# parent_altium-designer.net
KiCad netlist of a schematic drawn in Altium Designer
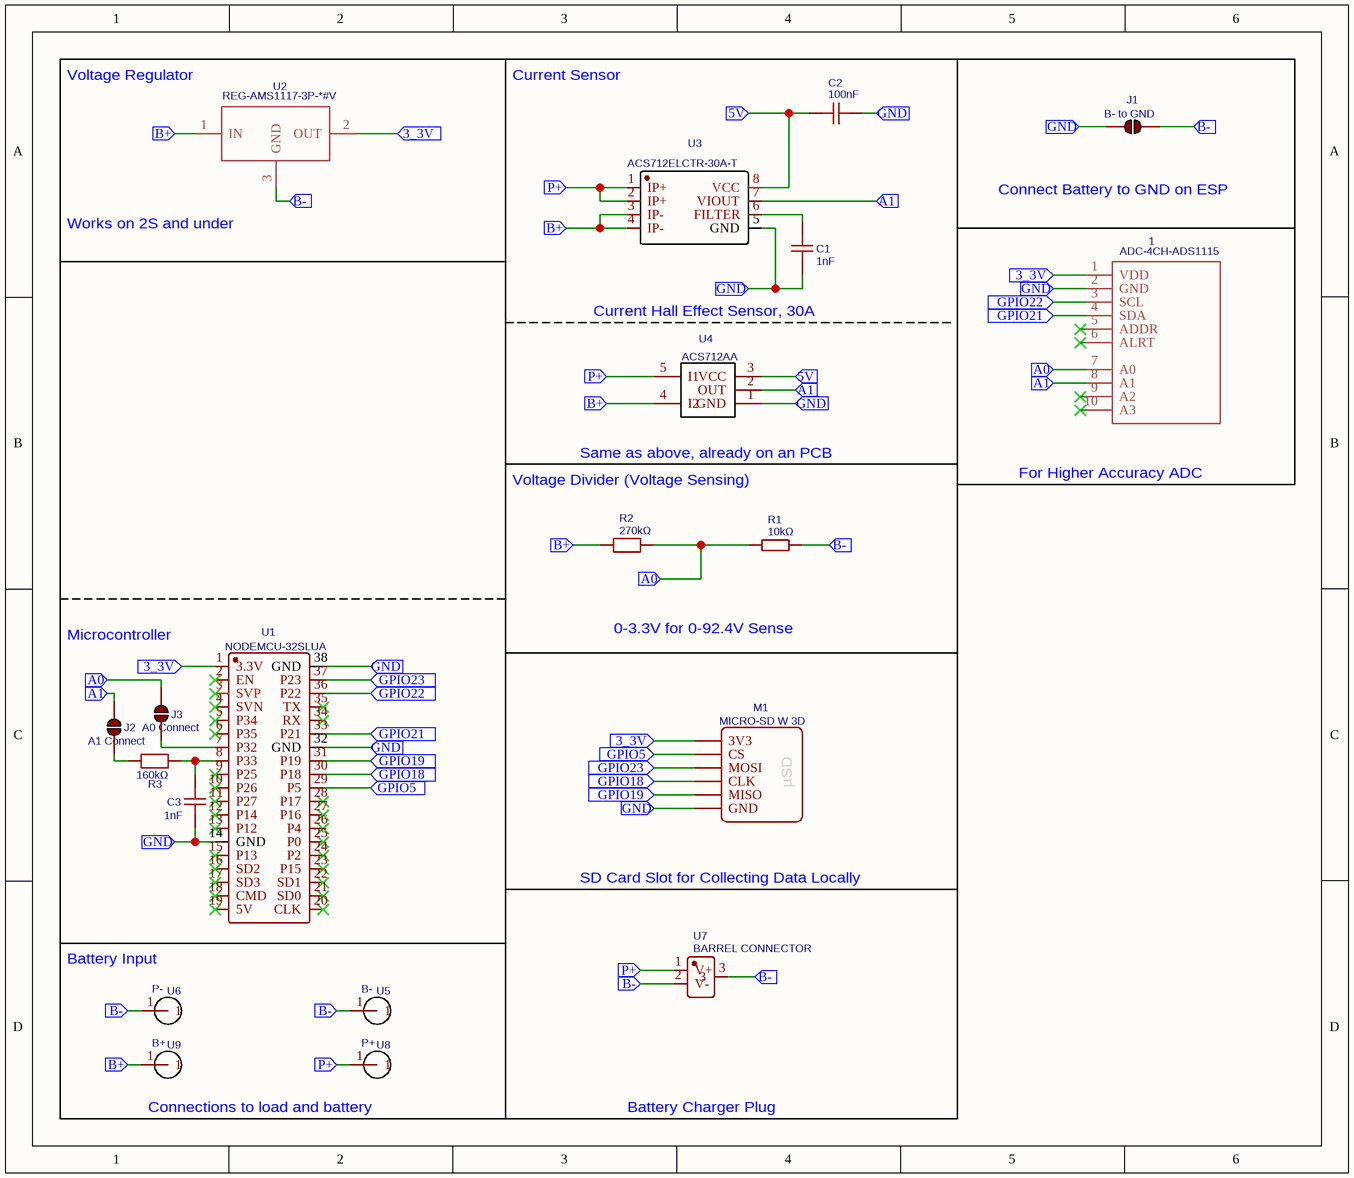
[diagram p0: parent_altium-designer.schdoc]

(export (version "E")
  (design (tool "Eeschema 10.0.6"))
  (components
    (comp (ref "1")
      (value "ADC-4CH-ADS1115")
      (fields (field (name "CONTRIBUTOR") "Tim Neuber"))
      (libsource (lib "altium-import") (part "root_0_ADC-4CH-ADS1115_"))
    )
    (comp (ref "C1")
      (value "1nF")
      (fields
        (field (name "MANUFACTURER") "KNSCHA(科尼盛)")
        (field (name "MANUFACTURER PART") "Y5P102K2KV16CC0224")
        (field (name "CONTRIBUTOR") "LCSC")
      )
      (libsource (lib "altium-import") (part "root_3_1nF_"))
    )
    (comp (ref "C2")
      (value "100nF")
      (fields
        (field (name "MANUFACTURER") "Dersonic(德尔创)")
        (field (name "MANUFACTURER PART") "CC1H104ZA1PD3F5O30MF")
        (field (name "CONTRIBUTOR") "LCSC")
      )
      (libsource (lib "altium-import") (part "root_1_100nF_"))
    )
    (comp (ref "C3")
      (value "1nF")
      (fields
        (field (name "MANUFACTURER") "KNSCHA(科尼盛)")
        (field (name "MANUFACTURER PART") "Y5P102K2KV16CC0224")
        (field (name "CONTRIBUTOR") "LCSC")
      )
      (libsource (lib "altium-import") (part "root_3_1nF_"))
    )
    (comp (ref "J1")
      (value "B- to GND")
      (fields (field (name "CONTRIBUTOR") "stefan.klaeui"))
      (libsource (lib "altium-import") (part "root_0_B- to GND_"))
    )
    (comp (ref "J2")
      (value "A1 Connect")
      (fields (field (name "CONTRIBUTOR") "stefan.klaeui"))
      (libsource (lib "altium-import") (part "root_3_A1 Connect_"))
    )
    (comp (ref "J3")
      (value "A0 Connect")
      (fields (field (name "CONTRIBUTOR") "stefan.klaeui"))
      (libsource (lib "altium-import") (part "root_3_A0 Connect_"))
    )
    (comp (ref "M1")
      (value "MICRO-SD W 3D")
      (fields (field (name "CONTRIBUTOR") "smurferman"))
      (libsource (lib "altium-import") (part "root_0_MICRO-SD W 3D_"))
    )
    (comp (ref "R1")
      (value "10kΩ")
      (fields
        (field (name "MANUFACTURER") "YAGEO(国巨)")
        (field (name "MANUFACTURER PART") "MFR-25FTE52-100K")
        (field (name "CONTRIBUTOR") "LCSC")
      )
      (libsource (lib "altium-import") (part "root_0_10kΩ_"))
    )
    (comp (ref "R2")
      (value "270kΩ")
      (fields
        (field (name "MANUFACTURER") "YAGEO(国巨)")
        (field (name "MANUFACTURER PART") "CFR-25JR-52-270K")
        (field (name "CONTRIBUTOR") "lcsc")
      )
      (libsource (lib "altium-import") (part "root_2_270kΩ_"))
    )
    (comp (ref "R3")
      (value "160kΩ")
      (fields
        (field (name "MANUFACTURER") "YAGEO(国巨)")
        (field (name "MANUFACTURER PART") "CFR-25JR-52-270K")
        (field (name "CONTRIBUTOR") "lcsc")
      )
      (libsource (lib "altium-import") (part "root_0_160kΩ_"))
    )
    (comp (ref "U1")
      (value "NODEMCU-32SLUA")
      (fields
        (field (name "MANUFACTURER") "Ai-Thinker(安信可)")
        (field (name "MANUFACTURER PART") "NodeMCU-32SLua")
        (field (name "CONTRIBUTOR") "lcsc")
      )
      (libsource (lib "altium-import") (part "root_0_NODEMCU-32SLUA_"))
    )
    (comp (ref "U2")
      (value "REG-AMS1117-3P-*#V")
      (fields (field (name "CONTRIBUTOR") "jboutin"))
      (libsource (lib "altium-import") (part "root_0_REG-AMS1117-3P-*#V_"))
    )
    (comp (ref "U3")
      (value "ACS712ELCTR-30A-T")
      (fields (field (name "MANUFACTURER") "ALLEGRO(美国埃戈罗)"))
      (libsource (lib "altium-import") (part "root_0_ACS712ELCTR-30A-T_"))
    )
    (comp (ref "U4")
      (value "ACS712AA")
      (fields (field (name "CONTRIBUTOR") "Ronald Rezal"))
      (libsource (lib "altium-import") (part "root_3_ACS712AA_"))
    )
    (comp (ref "U5")
      (value "B-")
      (fields (field (name "CONTRIBUTOR") "GORILLA-LINK"))
      (libsource (lib "altium-import") (part "root_0_B-_"))
    )
    (comp (ref "U6")
      (value "P-")
      (fields (field (name "CONTRIBUTOR") "GORILLA-LINK"))
      (libsource (lib "altium-import") (part "root_0_P-_"))
    )
    (comp (ref "U7")
      (value "BARREL CONNECTOR")
      (fields (field (name "CONTRIBUTOR") "scthornquist"))
      (libsource (lib "altium-import") (part "root_0_BARREL CONNECTOR_"))
    )
    (comp (ref "U8")
      (value "P+")
      (fields (field (name "CONTRIBUTOR") "GORILLA-LINK"))
      (libsource (lib "altium-import") (part "root_0_P+_"))
    )
    (comp (ref "U9")
      (value "B+")
      (fields (field (name "CONTRIBUTOR") "GORILLA-LINK"))
      (libsource (lib "altium-import") (part "root_0_B+_"))
    )
  )
  (nets
    (net (code "1") (name "/3_3V") (class "Default")
      (node (ref "1") (pin "1") (pinfunction "VDD_1") (pintype "passive"))
      (node (ref "M1") (pin "1") (pinfunction "3V3_1") (pintype "passive"))
      (node (ref "U1") (pin "1") (pinfunction "3.3V_1") (pintype "passive"))
      (node (ref "U2") (pin "2") (pinfunction "OUT_2") (pintype "passive"))
    )
    (net (code "2") (name "/5V") (class "Default")
      (node (ref "C2") (pin "2") (pinfunction "2_2") (pintype "passive"))
      (node (ref "U3") (pin "8") (pinfunction "VCC_8") (pintype "passive"))
      (node (ref "U4") (pin "3") (pinfunction "VCC_3") (pintype "passive"))
    )
    (net (code "3") (name "/A0") (class "Default")
      (node (ref "1") (pin "7") (pinfunction "A0_7") (pintype "passive"))
      (node (ref "J3") (pin "1") (pinfunction "1_1") (pintype "passive"))
      (node (ref "R1") (pin "1") (pinfunction "1_1") (pintype "passive"))
      (node (ref "R2") (pin "1") (pinfunction "1_1") (pintype "passive"))
    )
    (net (code "4") (name "/A1") (class "Default")
      (node (ref "1") (pin "8") (pinfunction "A1_8") (pintype "passive"))
      (node (ref "J2") (pin "1") (pinfunction "1_1") (pintype "passive"))
      (node (ref "U3") (pin "7") (pinfunction "VIOUT_7") (pintype "passive"))
      (node (ref "U4") (pin "2") (pinfunction "OUT_2") (pintype "passive"))
    )
    (net (code "5") (name "/B+") (class "Default")
      (node (ref "R2") (pin "2") (pinfunction "2_2") (pintype "passive"))
      (node (ref "U2") (pin "1") (pinfunction "IN_1") (pintype "passive"))
      (node (ref "U3") (pin "3") (pinfunction "IP-_3") (pintype "passive"))
      (node (ref "U3") (pin "4") (pinfunction "IP-_4") (pintype "passive"))
      (node (ref "U4") (pin "4") (pinfunction "I2_4") (pintype "passive"))
      (node (ref "U9") (pin "1") (pinfunction "1_1") (pintype "passive"))
    )
    (net (code "6") (name "/B-") (class "Default")
      (node (ref "J1") (pin "2") (pinfunction "2_2") (pintype "passive"))
      (node (ref "R1") (pin "2") (pinfunction "2_2") (pintype "passive"))
      (node (ref "U2") (pin "3") (pinfunction "GND_3") (pintype "passive"))
      (node (ref "U5") (pin "1") (pinfunction "1_1") (pintype "passive"))
      (node (ref "U6") (pin "1") (pinfunction "1_1") (pintype "passive"))
      (node (ref "U7") (pin "2") (pinfunction "V-_2") (pintype "passive"))
      (node (ref "U7") (pin "3") (pinfunction "3_3") (pintype "passive"))
    )
    (net (code "7") (name "/GND") (class "Default")
      (node (ref "1") (pin "2") (pinfunction "GND_2") (pintype "passive"))
      (node (ref "C1") (pin "2") (pinfunction "2_2") (pintype "passive"))
      (node (ref "C2") (pin "1") (pinfunction "1_1") (pintype "passive"))
      (node (ref "C3") (pin "2") (pinfunction "2_2") (pintype "passive"))
      (node (ref "J1") (pin "1") (pinfunction "1_1") (pintype "passive"))
      (node (ref "M1") (pin "6") (pinfunction "GND_6") (pintype "passive"))
      (node (ref "U1") (pin "14") (pinfunction "GND_14") (pintype "passive"))
      (node (ref "U1") (pin "32") (pinfunction "GND_32") (pintype "passive"))
      (node (ref "U1") (pin "38") (pinfunction "GND_38") (pintype "passive"))
      (node (ref "U3") (pin "5") (pinfunction "GND_5") (pintype "passive"))
      (node (ref "U4") (pin "1") (pinfunction "GND_1") (pintype "passive"))
    )
    (net (code "8") (name "/GPIO5") (class "Default")
      (node (ref "M1") (pin "2") (pinfunction "CS_2") (pintype "passive"))
      (node (ref "U1") (pin "29") (pinfunction "P5_29") (pintype "passive"))
    )
    (net (code "9") (name "/GPIO18") (class "Default")
      (node (ref "M1") (pin "4") (pinfunction "CLK_4") (pintype "passive"))
      (node (ref "U1") (pin "30") (pinfunction "P18_30") (pintype "passive"))
    )
    (net (code "10") (name "/GPIO19") (class "Default")
      (node (ref "M1") (pin "5") (pinfunction "MISO_5") (pintype "passive"))
      (node (ref "U1") (pin "31") (pinfunction "P19_31") (pintype "passive"))
    )
    (net (code "11") (name "/GPIO21") (class "Default")
      (node (ref "1") (pin "4") (pinfunction "SDA_4") (pintype "passive"))
      (node (ref "U1") (pin "33") (pinfunction "P21_33") (pintype "passive"))
    )
    (net (code "12") (name "/GPIO22") (class "Default")
      (node (ref "1") (pin "3") (pinfunction "SCL_3") (pintype "passive"))
      (node (ref "U1") (pin "36") (pinfunction "P22_36") (pintype "passive"))
    )
    (net (code "13") (name "/GPIO23") (class "Default")
      (node (ref "M1") (pin "3") (pinfunction "MOSI_3") (pintype "passive"))
      (node (ref "U1") (pin "37") (pinfunction "P23_37") (pintype "passive"))
    )
    (net (code "14") (name "/P+") (class "Default")
      (node (ref "U3") (pin "1") (pinfunction "IP+_1") (pintype "passive"))
      (node (ref "U3") (pin "2") (pinfunction "IP+_2") (pintype "passive"))
      (node (ref "U4") (pin "5") (pinfunction "I1_5") (pintype "passive"))
      (node (ref "U7") (pin "1") (pinfunction "V+_1") (pintype "passive"))
      (node (ref "U8") (pin "1") (pinfunction "1_1") (pintype "passive"))
    )
    (net (code "15") (name "Net-(J2-Pad2)") (class "Default")
      (node (ref "J2") (pin "2") (pinfunction "2_2") (pintype "passive"))
      (node (ref "R3") (pin "1") (pinfunction "1_1") (pintype "passive"))
    )
    (net (code "16") (name "Net-(U1-P32)") (class "Default")
      (node (ref "J3") (pin "2") (pinfunction "2_2") (pintype "passive"))
      (node (ref "U1") (pin "7") (pinfunction "P32_7") (pintype "passive"))
    )
    (net (code "17") (name "Net-(U1-P33)") (class "Default")
      (node (ref "C3") (pin "1") (pinfunction "1_1") (pintype "passive"))
      (node (ref "R3") (pin "2") (pinfunction "2_2") (pintype "passive"))
      (node (ref "U1") (pin "8") (pinfunction "P33_8") (pintype "passive"))
    )
    (net (code "18") (name "Net-(U3-FILTER)") (class "Default")
      (node (ref "C1") (pin "1") (pinfunction "1_1") (pintype "passive"))
      (node (ref "U3") (pin "6") (pinfunction "FILTER_6") (pintype "passive"))
    )
    (net (code "19") (name "unconnected-(1-A2-Pad9)") (class "Default")
      (node (ref "1") (pin "9") (pinfunction "A2_9") (pintype "passive+no_connect"))
    )
    (net (code "20") (name "unconnected-(1-A3-Pad10)") (class "Default")
      (node (ref "1") (pin "10") (pinfunction "A3_10") (pintype "passive+no_connect"))
    )
    (net (code "21") (name "unconnected-(1-ADDR-Pad5)") (class "Default")
      (node (ref "1") (pin "5") (pinfunction "ADDR_5") (pintype "passive+no_connect"))
    )
    (net (code "22") (name "unconnected-(1-ALRT-Pad6)") (class "Default")
      (node (ref "1") (pin "6") (pinfunction "ALRT_6") (pintype "passive+no_connect"))
    )
    (net (code "23") (name "unconnected-(U1-5V-Pad19)") (class "Default")
      (node (ref "U1") (pin "19") (pinfunction "5V_19") (pintype "passive+no_connect"))
    )
    (net (code "24") (name "unconnected-(U1-CLK-Pad20)") (class "Default")
      (node (ref "U1") (pin "20") (pinfunction "CLK_20") (pintype "passive+no_connect"))
    )
    (net (code "25") (name "unconnected-(U1-CMD-Pad18)") (class "Default")
      (node (ref "U1") (pin "18") (pinfunction "CMD_18") (pintype "passive+no_connect"))
    )
    (net (code "26") (name "unconnected-(U1-EN-Pad2)") (class "Default")
      (node (ref "U1") (pin "2") (pinfunction "EN_2") (pintype "passive+no_connect"))
    )
    (net (code "27") (name "unconnected-(U1-P0-Pad25)") (class "Default")
      (node (ref "U1") (pin "25") (pinfunction "P0_25") (pintype "passive+no_connect"))
    )
    (net (code "28") (name "unconnected-(U1-P2-Pad24)") (class "Default")
      (node (ref "U1") (pin "24") (pinfunction "P2_24") (pintype "passive+no_connect"))
    )
    (net (code "29") (name "unconnected-(U1-P4-Pad26)") (class "Default")
      (node (ref "U1") (pin "26") (pinfunction "P4_26") (pintype "passive+no_connect"))
    )
    (net (code "30") (name "unconnected-(U1-P12-Pad13)") (class "Default")
      (node (ref "U1") (pin "13") (pinfunction "P12_13") (pintype "passive+no_connect"))
    )
    (net (code "31") (name "unconnected-(U1-P13-Pad15)") (class "Default")
      (node (ref "U1") (pin "15") (pinfunction "P13_15") (pintype "passive+no_connect"))
    )
    (net (code "32") (name "unconnected-(U1-P14-Pad12)") (class "Default")
      (node (ref "U1") (pin "12") (pinfunction "P14_12") (pintype "passive+no_connect"))
    )
    (net (code "33") (name "unconnected-(U1-P15-Pad23)") (class "Default")
      (node (ref "U1") (pin "23") (pinfunction "P15_23") (pintype "passive+no_connect"))
    )
    (net (code "34") (name "unconnected-(U1-P16-Pad27)") (class "Default")
      (node (ref "U1") (pin "27") (pinfunction "P16_27") (pintype "passive+no_connect"))
    )
    (net (code "35") (name "unconnected-(U1-P17-Pad28)") (class "Default")
      (node (ref "U1") (pin "28") (pinfunction "P17_28") (pintype "passive+no_connect"))
    )
    (net (code "36") (name "unconnected-(U1-P25-Pad9)") (class "Default")
      (node (ref "U1") (pin "9") (pinfunction "P25_9") (pintype "passive+no_connect"))
    )
    (net (code "37") (name "unconnected-(U1-P26-Pad10)") (class "Default")
      (node (ref "U1") (pin "10") (pinfunction "P26_10") (pintype "passive+no_connect"))
    )
    (net (code "38") (name "unconnected-(U1-P27-Pad11)") (class "Default")
      (node (ref "U1") (pin "11") (pinfunction "P27_11") (pintype "passive+no_connect"))
    )
    (net (code "39") (name "unconnected-(U1-P34-Pad5)") (class "Default")
      (node (ref "U1") (pin "5") (pinfunction "P34_5") (pintype "passive+no_connect"))
    )
    (net (code "40") (name "unconnected-(U1-P35-Pad6)") (class "Default")
      (node (ref "U1") (pin "6") (pinfunction "P35_6") (pintype "passive+no_connect"))
    )
    (net (code "41") (name "unconnected-(U1-RX-Pad34)") (class "Default")
      (node (ref "U1") (pin "34") (pinfunction "RX_34") (pintype "passive+no_connect"))
    )
    (net (code "42") (name "unconnected-(U1-SD0-Pad21)") (class "Default")
      (node (ref "U1") (pin "21") (pinfunction "SD0_21") (pintype "passive+no_connect"))
    )
    (net (code "43") (name "unconnected-(U1-SD1-Pad22)") (class "Default")
      (node (ref "U1") (pin "22") (pinfunction "SD1_22") (pintype "passive+no_connect"))
    )
    (net (code "44") (name "unconnected-(U1-SD2-Pad16)") (class "Default")
      (node (ref "U1") (pin "16") (pinfunction "SD2_16") (pintype "passive+no_connect"))
    )
    (net (code "45") (name "unconnected-(U1-SD3-Pad17)") (class "Default")
      (node (ref "U1") (pin "17") (pinfunction "SD3_17") (pintype "passive+no_connect"))
    )
    (net (code "46") (name "unconnected-(U1-SVN-Pad4)") (class "Default")
      (node (ref "U1") (pin "4") (pinfunction "SVN_4") (pintype "passive+no_connect"))
    )
    (net (code "47") (name "unconnected-(U1-SVP-Pad3)") (class "Default")
      (node (ref "U1") (pin "3") (pinfunction "SVP_3") (pintype "passive+no_connect"))
    )
    (net (code "48") (name "unconnected-(U1-TX-Pad35)") (class "Default")
      (node (ref "U1") (pin "35") (pinfunction "TX_35") (pintype "passive+no_connect"))
    )
  )
)
